# Current_Driver_2.net
KiCad netlist of a schematic drawn in Altium Designer
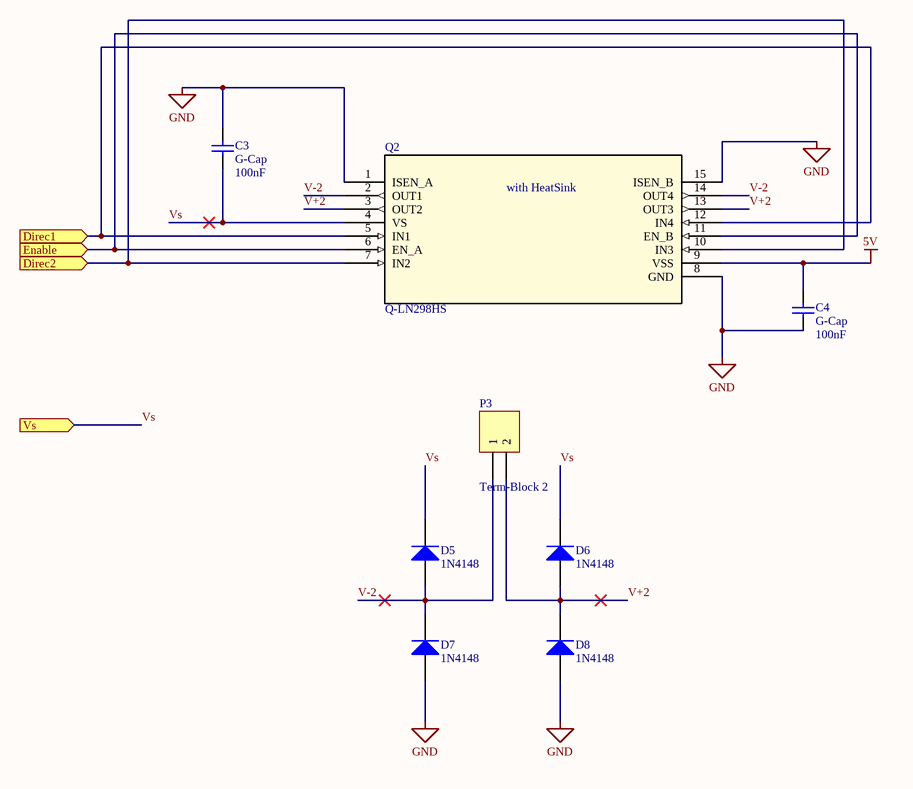
[diagram p0: Current_Driver_2.SchDoc]

(export (version "E")
  (design (tool "Eeschema 10.0.6"))
  (components
    (comp (ref "C3")
      (value "G-Cap")
      (footprint "Cap2.54mm_LGE1.0")
      (description "Capacitor (specify value)")
      (fields (field (name "ALTIUM_VALUE") "100nF") (field (name "PUBLISHER") "Altium Limited"))
      (libsource (lib "PartsDatabaseV16.1") (part "G-Cap"))
    )
    (comp (ref "C4")
      (value "G-Cap")
      (footprint "Cap2.54mm_LGE1.0")
      (description "Capacitor (specify value)")
      (fields (field (name "ALTIUM_VALUE") "100nF") (field (name "PUBLISHER") "Altium Limited"))
      (libsource (lib "PartsDatabaseV16.1") (part "G-Cap"))
    )
    (comp (ref "D5")
      (value "1N4148")
      (footprint "DO-41_XLGE1.2")
      (description "High-speed Diode")
      (libsource (lib "PartsDatabaseV16.1") (part "T-DiodeRect"))
    )
    (comp (ref "D6")
      (value "1N4148")
      (footprint "DO-41_XLGE1.2")
      (description "High-speed Diode")
      (libsource (lib "PartsDatabaseV16.1") (part "T-DiodeRect"))
    )
    (comp (ref "D7")
      (value "1N4148")
      (footprint "DO-41_XLGE1.2")
      (description "High-speed Diode")
      (libsource (lib "PartsDatabaseV16.1") (part "T-DiodeRect"))
    )
    (comp (ref "D8")
      (value "1N4148")
      (footprint "DO-41_XLGE1.2")
      (description "High-speed Diode")
      (libsource (lib "PartsDatabaseV16.1") (part "T-DiodeRect"))
    )
    (comp (ref "P3")
      (value "Term-Block 2")
      (footprint "TERM-BLOCK-5.08MM-2POS")
      (description "Terminal-Block 1x2")
      (fields (field (name "PUBLISHER") "Altium Limited"))
      (libsource (lib "PartsDatabaseV16.1") (part "C-Block2"))
    )
    (comp (ref "Q2")
      (value "Q-LN298HS")
      (footprint "Multiwatt15_V_ELEC391HS")
      (description "LN298 - IC Bridge Driver Par 15Multiwatt")
      (fields
        (field (name "MANUFACTURER_PART_NUMBER") "L298N")
        (field (name "COPYRIGHT") "Copyright (C) 2015 Accelerated Designs. All rights reserved")
      )
      (libsource (lib "Additional Parts 391") (part "Q-LN298HS"))
    )
  )
  (nets
    (net (code "1") (name "/Direc1") (class "Default")
      (node (ref "Q2") (pin "12") (pinfunction "IN4_12") (pintype "input"))
      (node (ref "Q2") (pin "5") (pinfunction "IN1_5") (pintype "input"))
    )
    (net (code "2") (name "/Direc2") (class "Default")
      (node (ref "Q2") (pin "10") (pinfunction "IN3_10") (pintype "input"))
      (node (ref "Q2") (pin "7") (pinfunction "IN2_7") (pintype "input"))
    )
    (net (code "3") (name "/Enable") (class "Default")
      (node (ref "Q2") (pin "11") (pinfunction "EN_B_11") (pintype "input"))
      (node (ref "Q2") (pin "6") (pinfunction "EN_A_6") (pintype "input"))
    )
    (net (code "4") (name "/V+2") (class "Default")
      (node (ref "D6") (pin "1") (pinfunction "A_1") (pintype "passive"))
      (node (ref "D8") (pin "2") (pinfunction "K_2") (pintype "passive"))
      (node (ref "P3") (pin "2") (pinfunction "2_2") (pintype "passive"))
      (node (ref "Q2") (pin "13") (pinfunction "OUT3_13") (pintype "output"))
      (node (ref "Q2") (pin "3") (pinfunction "OUT2_3") (pintype "output"))
    )
    (net (code "5") (name "/V-2") (class "Default")
      (node (ref "D5") (pin "1") (pinfunction "A_1") (pintype "passive"))
      (node (ref "D7") (pin "2") (pinfunction "K_2") (pintype "passive"))
      (node (ref "P3") (pin "1") (pinfunction "1_1") (pintype "passive"))
      (node (ref "Q2") (pin "14") (pinfunction "OUT4_14") (pintype "output"))
      (node (ref "Q2") (pin "2") (pinfunction "OUT1_2") (pintype "output"))
    )
    (net (code "6") (name "/Vs") (class "Default")
      (node (ref "C3") (pin "1") (pinfunction "1_1") (pintype "passive"))
      (node (ref "D5") (pin "2") (pinfunction "K_2") (pintype "passive"))
      (node (ref "D6") (pin "2") (pinfunction "K_2") (pintype "passive"))
      (node (ref "Q2") (pin "4") (pinfunction "VS_4") (pintype "power_in"))
    )
    (net (code "7") (name "5V") (class "Default")
      (node (ref "C4") (pin "2") (pinfunction "2_2") (pintype "passive"))
      (node (ref "Q2") (pin "9") (pinfunction "VSS_9") (pintype "power_in"))
    )
    (net (code "8") (name "GND") (class "Default")
      (node (ref "C3") (pin "2") (pinfunction "2_2") (pintype "passive"))
      (node (ref "C4") (pin "1") (pinfunction "1_1") (pintype "passive"))
      (node (ref "D7") (pin "1") (pinfunction "A_1") (pintype "passive"))
      (node (ref "D8") (pin "1") (pinfunction "A_1") (pintype "passive"))
      (node (ref "Q2") (pin "1") (pinfunction "ISEN_A_1") (pintype "passive"))
      (node (ref "Q2") (pin "15") (pinfunction "ISEN_B_15") (pintype "passive"))
      (node (ref "Q2") (pin "8") (pinfunction "GND_8") (pintype "power_in"))
    )
  )
)
